# robotShield.net
KiCad netlist of a schematic drawn in Altium Designer
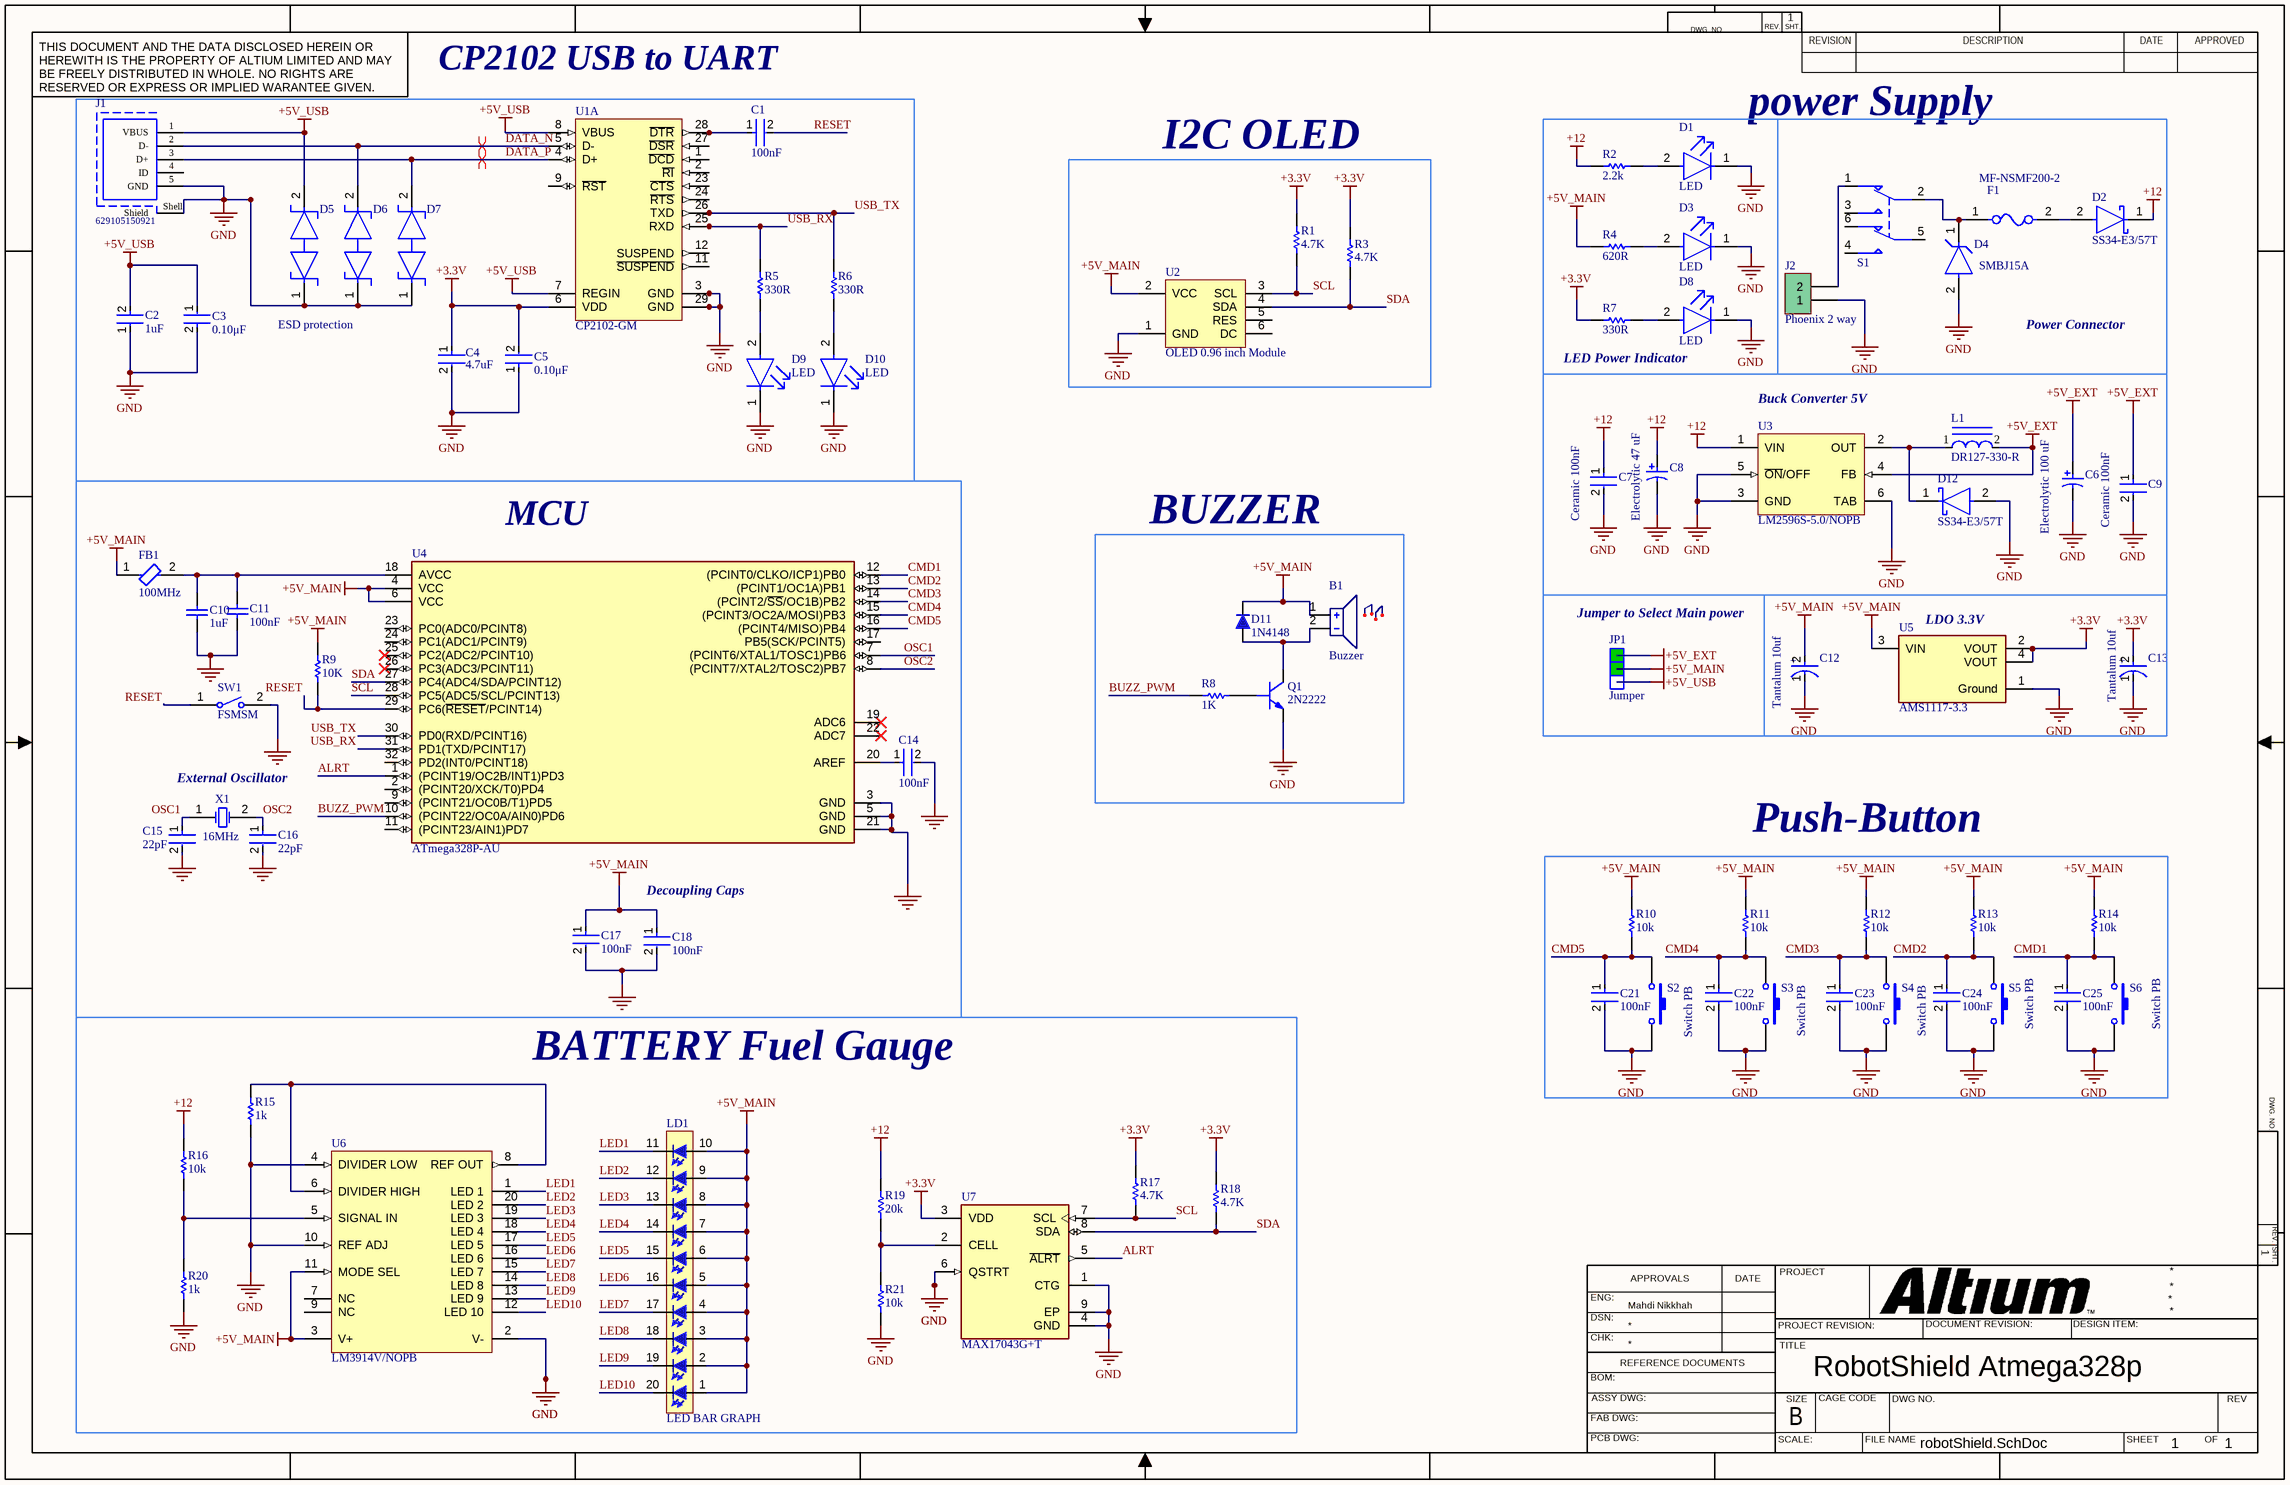
[diagram p0: robotShield.SchDoc]

(export (version "E")
  (design (tool "Eeschema 10.0.6"))
  (components
    (comp (ref "B1")
      (value "Buzzer")
      (footprint "Buzzer 3M")
      (libsource (lib "altium-import") (part "root_0_Buzzer New_"))
    )
    (comp (ref "C1")
      (value "100nF")
      (footprint "FP-GRM21B-0_15-MFG")
      (description "Chip Multilayer Ceramic Capacitors for General Purpose, 0805, 22uF, X5R, 15%, 20%, 6.3V")
      (fields (field (name "VOLTAGE") "6.3V") (field (name "TOLERANCE") "20%"))
      (libsource (lib "Altium Content Vault") (part "b4654b650e69147ec39a6b967a45e02"))
    )
    (comp (ref "C2")
      (value "1uF")
      (footprint "FP-GRM15-0_1-MFG")
      (description "CAP CER 1UF 10V X5R 0402")
      (fields
        (field (name "OCTOPART") "https://octopart.com/grm155r61a105ke15d-murata-197442")
        (field (name "MANUFACTURER PART NUMBER") "GRM155R61A105KE15D")
      )
      (libsource (lib "") (part "02cd4be3c70576c341d710602a673aa_1"))
    )
    (comp (ref "C3")
      (value "0.10μF")
      (footprint "FP-GRM15-MFG")
      (description "CAP CER 0.1UF 16V X7R 0402")
      (fields (field (name "MANUFACTURER PART NUMBER") "GRM155R71C104KA88D") (field (name "TOLERANCE") "10%"))
      (libsource (lib "") (part "236180d848d6139a670b325ea6854c9_1"))
    )
    (comp (ref "C4")
      (value "C1005X5R1A475K050BC")
      (footprint "FP-C1005-050-0_15-MFG")
      (description "CAP CER 4.7UF 10V X5R 0402")
      (fields (field (name "TOLERANCE") "10%") (field (name "CAPACITANCE") "4.7uF"))
      (libsource (lib "Altium Content Vault") (part "b4654b650e69147ec39a6b967a45e02"))
    )
    (comp (ref "C5")
      (value "0.10μF")
      (footprint "FP-GRM15-MFG")
      (description "CAP CER 0.1UF 16V X7R 0402")
      (fields (field (name "MANUFACTURER PART NUMBER") "GRM155R71C104KA88D") (field (name "TOLERANCE") "10%"))
      (libsource (lib "Altium Content Vault") (part "236180d848d6139a670b325ea6854c9"))
    )
    (comp (ref "C6")
      (value "Electrolytic 100 uF")
      (footprint "PNSC-EEEFK1C101P_L")
      (fields (field (name "MANUFACTURER") "Panasonic"))
      (libsource (lib "Altium Content Vault") (part "CAP-P-2"))
    )
    (comp (ref "C7")
      (value "Ceramic 100nF")
      (footprint "FP-1206-L_3_2_0_2-W_1_6_0-MFG")
      (description "General Purpose Ceramic Capacitor, 1206, 100nF, 10%, X7R, 15%, 50V")
      (fields (field (name "TOLERANCE") "10%") (field (name "VOLTAGE") "50V"))
      (libsource (lib "Altium Content Vault") (part "02cd4be3c70576c341d710602a673aa"))
    )
    (comp (ref "C8")
      (value "Electrolytic 47 uF")
      (footprint "PNSC-FT-V-53x53-2_V")
      (fields (field (name "PARTNUMBER") "EEE-FT1E470AR") (field (name "MANUFACTURER") "Panasonic"))
      (libsource (lib "Altium Content Vault") (part "PNSC-CAP-P-2"))
    )
    (comp (ref "C9")
      (value "Ceramic 100nF")
      (footprint "FP-1206-L_3_2_0_2-W_1_6_0-MFG")
      (description "General Purpose Ceramic Capacitor, 1206, 100nF, 10%, X7R, 15%, 50V")
      (fields (field (name "TOLERANCE") "10%") (field (name "VOLTAGE") "50V"))
      (libsource (lib "Altium Content Vault") (part "02cd4be3c70576c341d710602a673aa"))
    )
    (comp (ref "C10")
      (value "1uF")
      (footprint "CAPC3216X95X55NL15T25")
      (description "Chip Capacitor, 0.1 uF, +/- 10%, 50 V, -55 to 125 degC, 1206 (3216 Metric), RoHS, Tape and Reel")
      (fields (field (name "MANUFACTURER") "Murata"))
      (libsource (lib "Altium Content Vault") (part "CAP-NP-2"))
    )
    (comp (ref "C11")
      (value "100nF")
      (footprint "CAPC3216X95X55NL15T25")
      (description "Chip Capacitor, 0.1 uF, +/- 10%, 50 V, -55 to 125 degC, 1206 (3216 Metric), RoHS, Tape and Reel")
      (fields (field (name "MANUFACTURER") "Murata"))
      (libsource (lib "Altium Content Vault") (part "CAP-NP-2"))
    )
    (comp (ref "C12")
      (value "Tantalum 10uf")
      (footprint "FP-TAJA-MFG")
      (description "10uF 16V  ±10% 3Ω 1206  SMD Tantalum Capacitor")
      (fields (field (name "VOLTAGE") "16V") (field (name "TOLERANCE") "10%"))
      (libsource (lib "Altium Content Vault") (part "203bc49f2ac43e59fd269a8c329ed05"))
    )
    (comp (ref "C13")
      (value "Tantalum 10uf")
      (footprint "FP-TAJA-MFG")
      (description "10uF 16V  ±10% 3Ω 1206  SMD Tantalum Capacitor")
      (fields (field (name "VOLTAGE") "16V") (field (name "TOLERANCE") "10%"))
      (libsource (lib "Altium Content Vault") (part "203bc49f2ac43e59fd269a8c329ed05"))
    )
    (comp (ref "C14")
      (value "100nF")
      (footprint "FP-GRM21B-0_15-MFG")
      (description "Chip Multilayer Ceramic Capacitors for General Purpose, 0805, 22uF, X5R, 15%, 20%, 6.3V")
      (fields (field (name "VOLTAGE") "6.3V") (field (name "TOLERANCE") "20%"))
      (libsource (lib "Altium Content Vault") (part "b4654b650e69147ec39a6b967a45e02"))
    )
    (comp (ref "C15")
      (value "22pF")
      (footprint "FP-C1206C-EB-MFG")
      (description "CAP CER 22PF 100V 5% NP0 1206")
      (fields
        (field (name "MANUFACTURER PART NUMBER") "C1206C220J1GACTU")
        (field (name "MANUFACTURER") "KEMET")
      )
      (libsource (lib "Altium Content Vault") (part "b4654b650e69147ec39a6b967a45e02"))
    )
    (comp (ref "C16")
      (value "22pF")
      (footprint "FP-C1206C-EB-MFG")
      (description "CAP CER 22PF 100V 5% NP0 1206")
      (fields
        (field (name "MANUFACTURER PART NUMBER") "C1206C220J1GACTU")
        (field (name "MANUFACTURER") "KEMET")
      )
      (libsource (lib "Altium Content Vault") (part "b4654b650e69147ec39a6b967a45e02"))
    )
    (comp (ref "C17")
      (value "100nF")
      (footprint "FP-GRM21B-0_15-MFG")
      (description "Chip Multilayer Ceramic Capacitors for General Purpose, 0805, 22uF, X5R, 15%, 20%, 6.3V")
      (fields (field (name "VOLTAGE") "6.3V") (field (name "TOLERANCE") "20%"))
      (libsource (lib "Altium Content Vault") (part "b4654b650e69147ec39a6b967a45e02"))
    )
    (comp (ref "C18")
      (value "100nF")
      (footprint "FP-GRM21B-0_15-MFG")
      (description "Chip Multilayer Ceramic Capacitors for General Purpose, 0805, 22uF, X5R, 15%, 20%, 6.3V")
      (fields (field (name "VOLTAGE") "6.3V") (field (name "TOLERANCE") "20%"))
      (libsource (lib "Altium Content Vault") (part "b4654b650e69147ec39a6b967a45e02"))
    )
    (comp (ref "C21")
      (value "100nF")
      (footprint "FP-GRM21B-0_15-MFG")
      (description "Chip Multilayer Ceramic Capacitors for General Purpose, 0805, 22uF, X5R, 15%, 20%, 6.3V")
      (fields (field (name "VOLTAGE") "6.3V") (field (name "TOLERANCE") "20%"))
      (libsource (lib "Altium Content Vault") (part "b4654b650e69147ec39a6b967a45e02"))
    )
    (comp (ref "C22")
      (value "100nF")
      (footprint "FP-GRM21B-0_15-MFG")
      (description "Chip Multilayer Ceramic Capacitors for General Purpose, 0805, 22uF, X5R, 15%, 20%, 6.3V")
      (fields (field (name "VOLTAGE") "6.3V") (field (name "TOLERANCE") "20%"))
      (libsource (lib "Altium Content Vault") (part "b4654b650e69147ec39a6b967a45e02"))
    )
    (comp (ref "C23")
      (value "100nF")
      (footprint "FP-GRM21B-0_15-MFG")
      (description "Chip Multilayer Ceramic Capacitors for General Purpose, 0805, 22uF, X5R, 15%, 20%, 6.3V")
      (fields (field (name "VOLTAGE") "6.3V") (field (name "TOLERANCE") "20%"))
      (libsource (lib "Altium Content Vault") (part "b4654b650e69147ec39a6b967a45e02"))
    )
    (comp (ref "C24")
      (value "100nF")
      (footprint "FP-GRM21B-0_15-MFG")
      (description "Chip Multilayer Ceramic Capacitors for General Purpose, 0805, 22uF, X5R, 15%, 20%, 6.3V")
      (fields (field (name "VOLTAGE") "6.3V") (field (name "TOLERANCE") "20%"))
      (libsource (lib "Altium Content Vault") (part "b4654b650e69147ec39a6b967a45e02"))
    )
    (comp (ref "C25")
      (value "100nF")
      (footprint "FP-GRM21B-0_15-MFG")
      (description "Chip Multilayer Ceramic Capacitors for General Purpose, 0805, 22uF, X5R, 15%, 20%, 6.3V")
      (fields (field (name "VOLTAGE") "6.3V") (field (name "TOLERANCE") "20%"))
      (libsource (lib "Altium Content Vault") (part "b4654b650e69147ec39a6b967a45e02"))
    )
    (comp (ref "D1")
      (value "LED")
      (footprint "FP-HSMG-C150-MFG")
      (description "LED GREEN DIFFUSED 1206 SMD")
      (fields (field (name "MANUFACTURER PART NUMBER") "HSMG-C150") (field (name "MANUFACTURER") "Broadcom"))
      (libsource (lib "Altium Content Vault") (part "8706943c75ba83719d021d2fdc84c58"))
    )
    (comp (ref "D2")
      (value "SS34-E3/57T")
      (footprint "FP-95402-MFG")
      (description "DIODE SCHOTTKY 40V 3A DO214AB")
      (fields
        (field (name "MANUFACTURER") "Vishay")
        (field (name "OCTOPART") "https://octopart.com/ss34-e3%2F57t-vishay-39552907")
      )
      (libsource (lib "Altium Content Vault") (part "1d6ec82d83fb6aee721767c19dac4b9"))
    )
    (comp (ref "D3")
      (value "LED")
      (footprint "FP-HSMG-C150-MFG")
      (description "LED GREEN DIFFUSED 1206 SMD")
      (fields (field (name "MANUFACTURER PART NUMBER") "HSMG-C150") (field (name "MANUFACTURER") "Broadcom"))
      (libsource (lib "Altium Content Vault") (part "8706943c75ba83719d021d2fdc84c58"))
    )
    (comp (ref "D4")
      (value "SMBJ15A")
      (footprint "FP-SMBJ-MFG")
      (description "TVS DIODE 15VWM 24.4VC SMB")
      (libsource (lib "Altium Content Vault") (part "f813f71cba58e380607f5dd3caf9714"))
    )
    (comp (ref "D5")
      (value "TPD1E10B06DPYR")
      (footprint "FP-DPY0002A-MFG")
      (description "TVS DIODE 5.5V 14V 2X1SON")
      (libsource (lib "Altium Content Vault") (part "208e19b57522434895fa003e5d5b197"))
    )
    (comp (ref "D6")
      (value "TPD1E10B06DPYR")
      (footprint "FP-DPY0002A-MFG")
      (description "TVS DIODE 5.5V 14V 2X1SON")
      (libsource (lib "Altium Content Vault") (part "208e19b57522434895fa003e5d5b197"))
    )
    (comp (ref "D7")
      (value "TPD1E10B06DPYR")
      (footprint "FP-DPY0002A-MFG")
      (description "TVS DIODE 5.5V 14V 2X1SON")
      (libsource (lib "Altium Content Vault") (part "208e19b57522434895fa003e5d5b197"))
    )
    (comp (ref "D8")
      (value "LED")
      (footprint "FP-HSMG-C150-MFG")
      (description "LED GREEN DIFFUSED 1206 SMD")
      (fields (field (name "MANUFACTURER PART NUMBER") "HSMG-C150") (field (name "MANUFACTURER") "Broadcom"))
      (libsource (lib "Altium Content Vault") (part "8706943c75ba83719d021d2fdc84c58"))
    )
    (comp (ref "D9")
      (value "LED")
      (footprint "FP-HSMG-C150-MFG")
      (description "LED GREEN DIFFUSED 1206 SMD")
      (fields (field (name "MANUFACTURER PART NUMBER") "HSMG-C150") (field (name "MANUFACTURER") "Broadcom"))
      (libsource (lib "Altium Content Vault") (part "8706943c75ba83719d021d2fdc84c58"))
    )
    (comp (ref "D10")
      (value "LED")
      (footprint "FP-HSMG-C150-MFG")
      (description "LED GREEN DIFFUSED 1206 SMD")
      (fields (field (name "MANUFACTURER PART NUMBER") "HSMG-C150") (field (name "MANUFACTURER") "Broadcom"))
      (libsource (lib "Altium Content Vault") (part "8706943c75ba83719d021d2fdc84c58"))
    )
    (comp (ref "D11")
      (value "1N4148")
      (footprint "SOD-123")
      (libsource (lib "altium-import") (part "root_1_1N4148_"))
    )
    (comp (ref "D12")
      (value "SS34-E3/57T")
      (footprint "FP-95402-MFG")
      (description "DIODE SCHOTTKY 40V 3A DO214AB")
      (fields
        (field (name "MANUFACTURER") "Vishay")
        (field (name "OCTOPART") "https://octopart.com/ss34-e3%2F57t-vishay-39552907")
      )
      (libsource (lib "Altium Content Vault") (part "1d6ec82d83fb6aee721767c19dac4b9"))
    )
    (comp (ref "F1")
      (value "MF-NSMF200-2")
      (footprint "FP-MF-NSMF200-2-MFG")
      (description "PTC RESET FUSE 12V 2A 1206")
      (fields
        (field (name "MANUFACTURER") "Bourns Inc.")
        (field (name "OCTOPART") "https://octopart.com/mf-nsmf200-2-bourns-90790")
      )
      (libsource (lib "Altium Content Vault") (part "5bcf9b9f640e542cf0359d10258e979"))
    )
    (comp (ref "FB1")
      (value "100MHz")
      (footprint "FP-BLM21-0_2-t0_85-e0_5-IPC_A")
      (description "FERRITE BEAD 120 OHM 0805 1LN")
      (fields (field (name "TOLERANCE") "25%"))
      (libsource (lib "Altium Content Vault") (part "5f30dd21d616792df468990f7003faa"))
    )
    (comp (ref "J1")
      (value "629105150921")
      (footprint "629105150921")
      (description "Micro USB 2.0 Type AB Receptacle WR-COM, Horizontal, SMT")
      (fields (field (name "PUBLISHER") "Wurth Elektronik"))
      (libsource (lib "USB") (part "629105150921"))
    )
    (comp (ref "J2")
      (value "Phoenix 2 way")
      (footprint "Phoenix 2 way 5.08mm V")
      (libsource (lib "altium-import") (part "root_1_Phoenix 2 way_"))
    )
    (comp (ref "JP1")
      (value "Jumper")
      (footprint "jumper selector")
      (description "Jumper Selector")
      (libsource (lib "altium-import") (part "root_0_Jumper Selector_"))
    )
    (comp (ref "L1")
      (value "DR127-330-R")
      (footprint "FP-DR127-MFG")
      (description "DR127-330-R Inductor Power Shielded Drum Core 33uH 20% 100KHz Ferrite 3.23A 60mOhm DCR T/R")
      (fields (field (name "TOLERANCE") "20%"))
      (libsource (lib "Altium Content Vault") (part "595efa879b4242f50b2b19a2702faec"))
    )
    (comp (ref "LD1")
      (value "LED BAR GRAPH")
      (footprint "LED BAR GRAPH W")
      (libsource (lib "altium-import") (part "root_2_LED BAR GRAPH_"))
    )
    (comp (ref "Q1")
      (value "2N2222")
      (footprint "SOT-23")
      (libsource (lib "altium-import") (part "root_0_2N2222_"))
    )
    (comp (ref "R1")
      (value "4.7K")
      (footprint "RESC2013X60X35ML10T20")
      (description "Chip Resistor, 1 KOhm, +/- 1%, 125 mW, -55 to 155 degC, 0805 (2012 Metric), RoHS, Tape and Reel")
      (fields (field (name "TOLERANCE") "1%") (field (name "MANUFACTURER") "Yageo"))
      (libsource (lib "Altium Content Vault") (part "RES-2"))
    )
    (comp (ref "R2")
      (value "2.2k")
      (footprint "RESC2013X60X35ML10T20")
      (description "Chip Resistor, 1 KOhm, +/- 1%, 125 mW, -55 to 155 degC, 0805 (2012 Metric), RoHS, Tape and Reel")
      (fields (field (name "TOLERANCE") "1%") (field (name "MANUFACTURER") "Yageo"))
      (libsource (lib "Altium Content Vault") (part "RES-2"))
    )
    (comp (ref "R3")
      (value "4.7K")
      (footprint "RESC2013X60X35ML10T20")
      (description "Chip Resistor, 1 KOhm, +/- 1%, 125 mW, -55 to 155 degC, 0805 (2012 Metric), RoHS, Tape and Reel")
      (fields (field (name "TOLERANCE") "1%") (field (name "MANUFACTURER") "Yageo"))
      (libsource (lib "Altium Content Vault") (part "RES-2"))
    )
    (comp (ref "R4")
      (value "620R")
      (footprint "RESC2013X60X35ML10T20")
      (description "Chip Resistor, 1 KOhm, +/- 1%, 125 mW, -55 to 155 degC, 0805 (2012 Metric), RoHS, Tape and Reel")
      (fields (field (name "TOLERANCE") "1%") (field (name "MANUFACTURER") "Yageo"))
      (libsource (lib "Altium Content Vault") (part "RES-2"))
    )
    (comp (ref "R5")
      (value "330R")
      (footprint "RESC2013X60X35ML10T20")
      (description "Chip Resistor, 1 KOhm, +/- 1%, 125 mW, -55 to 155 degC, 0805 (2012 Metric), RoHS, Tape and Reel")
      (fields (field (name "TOLERANCE") "1%") (field (name "MANUFACTURER") "Yageo"))
      (libsource (lib "Altium Content Vault") (part "RES-2"))
    )
    (comp (ref "R6")
      (value "330R")
      (footprint "RESC2013X60X35ML10T20")
      (description "Chip Resistor, 1 KOhm, +/- 1%, 125 mW, -55 to 155 degC, 0805 (2012 Metric), RoHS, Tape and Reel")
      (fields (field (name "TOLERANCE") "1%") (field (name "MANUFACTURER") "Yageo"))
      (libsource (lib "Altium Content Vault") (part "RES-2"))
    )
    (comp (ref "R7")
      (value "330R")
      (footprint "RESC2013X60X35ML10T20")
      (description "Chip Resistor, 1 KOhm, +/- 1%, 125 mW, -55 to 155 degC, 0805 (2012 Metric), RoHS, Tape and Reel")
      (fields (field (name "TOLERANCE") "1%") (field (name "MANUFACTURER") "Yageo"))
      (libsource (lib "Altium Content Vault") (part "RES-2"))
    )
    (comp (ref "R8")
      (value "1K")
      (footprint "RESC2013X60X35ML10T20")
      (description "Chip Resistor, 1 KOhm, +/- 1%, 125 mW, -55 to 155 degC, 0805 (2012 Metric), RoHS, Tape and Reel")
      (fields (field (name "TOLERANCE") "1%") (field (name "MANUFACTURER") "Yageo"))
      (libsource (lib "Altium Content Vault") (part "RES-2"))
    )
    (comp (ref "R9")
      (value "10K")
      (footprint "RESC3116X65X40ML10T20")
      (description "Chip Resistor, 10 KOhm, +/- 1%, 0.25 W, -55 to 155 degC, 1206 (3216 Metric), RoHS, Tape and Reel")
      (fields (field (name "TOLERANCE") "1%") (field (name "MANUFACTURER") "Yageo"))
      (libsource (lib "Altium Content Vault") (part "RES-2"))
    )
    (comp (ref "R10")
      (value "10k")
      (footprint "RESC2013X60X35ML10T20")
      (description "Chip Resistor, 1 KOhm, +/- 1%, 125 mW, -55 to 155 degC, 0805 (2012 Metric), RoHS, Tape and Reel")
      (fields (field (name "TOLERANCE") "1%") (field (name "MANUFACTURER") "Yageo"))
      (libsource (lib "Altium Content Vault") (part "RES-2"))
    )
    (comp (ref "R11")
      (value "10k")
      (footprint "RESC2013X60X35ML10T20")
      (description "Chip Resistor, 1 KOhm, +/- 1%, 125 mW, -55 to 155 degC, 0805 (2012 Metric), RoHS, Tape and Reel")
      (fields (field (name "TOLERANCE") "1%") (field (name "MANUFACTURER") "Yageo"))
      (libsource (lib "Altium Content Vault") (part "RES-2"))
    )
    (comp (ref "R12")
      (value "10k")
      (footprint "RESC2013X60X35ML10T20")
      (description "Chip Resistor, 1 KOhm, +/- 1%, 125 mW, -55 to 155 degC, 0805 (2012 Metric), RoHS, Tape and Reel")
      (fields (field (name "TOLERANCE") "1%") (field (name "MANUFACTURER") "Yageo"))
      (libsource (lib "Altium Content Vault") (part "RES-2"))
    )
    (comp (ref "R13")
      (value "10k")
      (footprint "RESC2013X60X35ML10T20")
      (description "Chip Resistor, 1 KOhm, +/- 1%, 125 mW, -55 to 155 degC, 0805 (2012 Metric), RoHS, Tape and Reel")
      (fields (field (name "TOLERANCE") "1%") (field (name "MANUFACTURER") "Yageo"))
      (libsource (lib "Altium Content Vault") (part "RES-2"))
    )
    (comp (ref "R14")
      (value "10k")
      (footprint "RESC2013X60X35ML10T20")
      (description "Chip Resistor, 1 KOhm, +/- 1%, 125 mW, -55 to 155 degC, 0805 (2012 Metric), RoHS, Tape and Reel")
      (fields (field (name "TOLERANCE") "1%") (field (name "MANUFACTURER") "Yageo"))
      (libsource (lib "Altium Content Vault") (part "RES-2"))
    )
    (comp (ref "R15")
      (value "1k")
      (footprint "RESC2013X60X35ML10T20")
      (description "Chip Resistor, 1 KOhm, +/- 1%, 125 mW, -55 to 155 degC, 0805 (2012 Metric), RoHS, Tape and Reel")
      (fields (field (name "TOLERANCE") "1%") (field (name "MANUFACTURER") "Yageo"))
      (libsource (lib "Altium Content Vault") (part "RES-2"))
    )
    (comp (ref "R16")
      (value "10k")
      (footprint "RESC2013X60X35ML10T20")
      (description "Chip Resistor, 1 KOhm, +/- 1%, 125 mW, -55 to 155 degC, 0805 (2012 Metric), RoHS, Tape and Reel")
      (fields (field (name "TOLERANCE") "1%") (field (name "MANUFACTURER") "Yageo"))
      (libsource (lib "Altium Content Vault") (part "RES-2"))
    )
    (comp (ref "R17")
      (value "4.7K")
      (footprint "RESC2013X60X35ML10T20")
      (description "Chip Resistor, 1 KOhm, +/- 1%, 125 mW, -55 to 155 degC, 0805 (2012 Metric), RoHS, Tape and Reel")
      (fields (field (name "TOLERANCE") "1%") (field (name "MANUFACTURER") "Yageo"))
      (libsource (lib "Altium Content Vault") (part "RES-2"))
    )
    (comp (ref "R18")
      (value "4.7K")
      (footprint "RESC2013X60X35ML10T20")
      (description "Chip Resistor, 1 KOhm, +/- 1%, 125 mW, -55 to 155 degC, 0805 (2012 Metric), RoHS, Tape and Reel")
      (fields (field (name "TOLERANCE") "1%") (field (name "MANUFACTURER") "Yageo"))
      (libsource (lib "Altium Content Vault") (part "RES-2"))
    )
    (comp (ref "R19")
      (value "20k")
      (footprint "RESC2013X60X35ML10T20")
      (description "Chip Resistor, 1 KOhm, +/- 1%, 125 mW, -55 to 155 degC, 0805 (2012 Metric), RoHS, Tape and Reel")
      (fields (field (name "TOLERANCE") "1%") (field (name "MANUFACTURER") "Yageo"))
      (libsource (lib "Altium Content Vault") (part "RES-2"))
    )
    (comp (ref "R20")
      (value "1k")
      (footprint "RESC2013X60X35ML10T20")
      (description "Chip Resistor, 1 KOhm, +/- 1%, 125 mW, -55 to 155 degC, 0805 (2012 Metric), RoHS, Tape and Reel")
      (fields (field (name "TOLERANCE") "1%") (field (name "MANUFACTURER") "Yageo"))
      (libsource (lib "Altium Content Vault") (part "RES-2"))
    )
    (comp (ref "R21")
      (value "10k")
      (footprint "RESC2013X60X35ML10T20")
      (description "Chip Resistor, 1 KOhm, +/- 1%, 125 mW, -55 to 155 degC, 0805 (2012 Metric), RoHS, Tape and Reel")
      (fields (field (name "TOLERANCE") "1%") (field (name "MANUFACTURER") "Yageo"))
      (libsource (lib "Altium Content Vault") (part "RES-2"))
    )
    (comp (ref "S1")
      (value "Double Switch")
      (footprint "Switch - DPDT")
      (description "DPDT Switch")
      (fields (field (name "DESIGNER") "Eng. Saeid Jorablo"))
      (libsource (lib "altium-import") (part "root_0_SW_DPDT_"))
    )
    (comp (ref "S2")
      (value "Switch PB")
      (footprint "SW-PB")
      (description "Push Button Switch")
      (libsource (lib "General 2") (part "Switch PB"))
    )
    (comp (ref "S3")
      (value "Switch PB")
      (footprint "SW-PB")
      (description "Push Button Switch")
      (libsource (lib "General 2") (part "Switch PB"))
    )
    (comp (ref "S4")
      (value "Switch PB")
      (footprint "SW-PB")
      (description "Push Button Switch")
      (libsource (lib "General 2") (part "Switch PB"))
    )
    (comp (ref "S5")
      (value "Switch PB")
      (footprint "SW-PB")
      (description "Push Button Switch")
      (libsource (lib "General 2") (part "Switch PB"))
    )
    (comp (ref "S6")
      (value "Switch PB")
      (footprint "SW-PB")
      (description "Push Button Switch")
      (libsource (lib "General 2") (part "Switch PB"))
    )
    (comp (ref "SW1")
      (value "FSMSM")
      (footprint "TECO-FSMSM-2_V")
      (description "FSMSM Push Button Switch, 50 mA, -35 to 85 degC, 2-Pin SMD, RoHS, Bulk")
      (fields (field (name "MANUFACTURER") "TE Connectivity"))
      (libsource (lib "Altium Content Vault") (part "SW-SPST-2_C"))
    )
    (comp (ref "U1")
      (value "CP2102-GM")
      (footprint "SLAB-QFN-28-3125x3125TP_N")
      (description "Single-Chip USB to UART Bridge, 1024 Bytes EEPROM, -40 to 85 degC, 28-pin QFN, Tube")
      (fields (field (name "MANUFACTURER") "Silicon Labs"))
      (libsource (lib "Altium Content Vault") (part "SLAB-CP210X-QFN-28-29"))
    )
    (comp (ref "U2")
      (value "OLED 0.96 inch Module")
      (footprint "OLED 0.96 inch Module")
      (libsource (lib "altium-import") (part "root_0_OLED 0.96 inch Module_"))
    )
    (comp (ref "U3")
      (value "LM2596S-5.0/NOPB")
      (footprint "KTT0005B_M")
      (description "SIMPLE SWITCHER® Power Converter 150 KHz 3A Step-Down Voltage Regulator, 5-pin TO-263, Pb-Free")
      (fields (field (name "MANUFACTURER") "Texas Instruments"))
      (libsource (lib "Altium Content Vault") (part "PM-REG-LM2575HVS-12"))
    )
    (comp (ref "U4")
      (value "ATmega328P-AU")
      (footprint "FP-32A-MFG")
      (description "IC MCU 8BIT 32KB FLASH 32TQFP")
      (fields
        (field (name "MANUFACTURER") "Microchip")
        (field (name "OCTOPART") "https://octopart.com/atmega328p-au-microchip-77760215")
      )
      (libsource (lib "Altium Content Vault") (part "f5fbdcb2c0c597ef7d3dd1575aef21a"))
    )
    (comp (ref "U5")
      (value "AMS1117-3.3")
      (footprint "FP-AMS1117-IPC_C")
      (description "LDO Voltage Regulators 1A, 3.3V")
      (fields
        (field (name "OCTOPART") "https://octopart.com/ams1117-3.3-advanced+monolithic+systems-25899300")
        (field (name "MANUFACTURER") "Advanced Monolithic Systems")
      )
      (libsource (lib "Altium Content Vault") (part "8bdbb5f8e77002000e30dd2845d0354"))
    )
    (comp (ref "U6")
      (value "LM3914V/NOPB")
      (footprint "FN0020A_L")
      (description "Dot/Bar Display Driver, 20-pin PLCC, Pb-Free")
      (fields (field (name "MANUFACTURER") "Texas Instruments"))
      (libsource (lib "Altium Content Vault") (part "IN-DD-LM3914-20"))
    )
    (comp (ref "U7")
      (value "MAX17043G+T")
      (footprint "FP-T823-1-MFG")
      (description "IC 2-WIRE FG MODEL GAUGE LO BATT")
      (fields
        (field (name "MANUFACTURER") "Maxim")
        (field (name "OCTOPART") "https://octopart.com/max17043g%2Bt-maxim+integrated-43979038")
      )
      (libsource (lib "Altium Content Vault") (part "35642440c5a18a865b7fad9439d5373"))
    )
    (comp (ref "X1")
      (value "16MHz")
      (footprint "FOX-FOXSDLF160-20_V")
      (libsource (lib "Altium Content Vault") (part "XTAL_1-2-2"))
    )
  )
  (nets
    (net (code "1") (name "+3.3V") (class "Default")
      (node (ref "C13") (pin "2") (pinfunction "A_2") (pintype "passive"))
      (node (ref "C4") (pin "1") (pinfunction "1_1") (pintype "passive"))
      (node (ref "C5") (pin "2") (pinfunction "2_2") (pintype "passive"))
      (node (ref "R1") (pin "2") (pinfunction "2_2") (pintype "passive"))
      (node (ref "R17") (pin "2") (pinfunction "2_2") (pintype "passive"))
      (node (ref "R18") (pin "2") (pinfunction "2_2") (pintype "passive"))
      (node (ref "R3") (pin "2") (pinfunction "2_2") (pintype "passive"))
      (node (ref "R7") (pin "1") (pinfunction "1_1") (pintype "passive"))
      (node (ref "U1") (pin "6") (pinfunction "VDD_6") (pintype "power_in"))
      (node (ref "U5") (pin "2") (pinfunction "VOUT_2") (pintype "passive"))
      (node (ref "U5") (pin "4") (pinfunction "VOUT_4") (pintype "passive"))
      (node (ref "U7") (pin "3") (pinfunction "VDD_3") (pintype "power_in"))
    )
    (net (code "2") (name "+5V_EXT") (class "Default")
      (node (ref "C6") (pin "1") (pinfunction "1_1") (pintype "passive"))
      (node (ref "C9") (pin "1") (pinfunction "1_1") (pintype "passive"))
      (node (ref "JP1") (pin "1") (pinfunction "1_1") (pintype "passive"))
      (node (ref "L1") (pin "2") (pinfunction "2_2") (pintype "passive"))
      (node (ref "U3") (pin "4") (pinfunction "FB_4") (pintype "input"))
    )
    (net (code "3") (name "+5V_MAIN") (class "Default")
      (node (ref "B1") (pin "1") (pinfunction "1_1") (pintype "passive"))
      (node (ref "C12") (pin "2") (pinfunction "A_2") (pintype "passive"))
      (node (ref "C17") (pin "1") (pinfunction "1_1") (pintype "passive"))
      (node (ref "C18") (pin "1") (pinfunction "1_1") (pintype "passive"))
      (node (ref "D11") (pin "2") (pinfunction "K_2") (pintype "passive"))
      (node (ref "FB1") (pin "1") (pinfunction "1_1") (pintype "passive"))
      (node (ref "JP1") (pin "2") (pinfunction "2_2") (pintype "passive"))
      (node (ref "LD1") (pin "1") (pinfunction "A_1") (pintype "passive"))
      (node (ref "LD1") (pin "10") (pinfunction "A_10") (pintype "passive"))
      (node (ref "LD1") (pin "2") (pinfunction "A_2") (pintype "passive"))
      (node (ref "LD1") (pin "3") (pinfunction "A_3") (pintype "passive"))
      (node (ref "LD1") (pin "4") (pinfunction "A_4") (pintype "passive"))
      (node (ref "LD1") (pin "5") (pinfunction "A_5") (pintype "passive"))
      (node (ref "LD1") (pin "6") (pinfunction "A_6") (pintype "passive"))
      (node (ref "LD1") (pin "7") (pinfunction "A_7") (pintype "passive"))
      (node (ref "LD1") (pin "8") (pinfunction "A_8") (pintype "passive"))
      (node (ref "LD1") (pin "9") (pinfunction "A_9") (pintype "passive"))
      (node (ref "R10") (pin "2") (pinfunction "2_2") (pintype "passive"))
      (node (ref "R11") (pin "2") (pinfunction "2_2") (pintype "passive"))
      (node (ref "R12") (pin "2") (pinfunction "2_2") (pintype "passive"))
      (node (ref "R13") (pin "2") (pinfunction "2_2") (pintype "passive"))
      (node (ref "R14") (pin "2") (pinfunction "2_2") (pintype "passive"))
      (node (ref "R4") (pin "1") (pinfunction "1_1") (pintype "passive"))
      (node (ref "R9") (pin "1") (pinfunction "1_1") (pintype "passive"))
      (node (ref "U2") (pin "2") (pinfunction "VCC_2") (pintype "passive"))
      (node (ref "U4") (pin "4") (pinfunction "VCC_4") (pintype "power_in"))
      (node (ref "U4") (pin "6") (pinfunction "VCC_6") (pintype "power_in"))
      (node (ref "U5") (pin "3") (pinfunction "VIN_3") (pintype "power_in"))
      (node (ref "U6") (pin "11") (pinfunction "MODE_SEL_11") (pintype "input"))
      (node (ref "U6") (pin "3") (pinfunction "V+_3") (pintype "power_in"))
    )
    (net (code "4") (name "+5V_USB") (class "Default")
      (node (ref "C2") (pin "2") (pinfunction "2_2") (pintype "passive"))
      (node (ref "C3") (pin "1") (pinfunction "1_1") (pintype "passive"))
      (node (ref "D5") (pin "2") (pinfunction "2_2") (pintype "passive"))
      (node (ref "J1") (pin "1") (pinfunction "VBUS_1") (pintype "passive"))
      (node (ref "JP1") (pin "3") (pinfunction "3_3") (pintype "passive"))
      (node (ref "U1") (pin "7") (pinfunction "REGIN_7") (pintype "power_in"))
      (node (ref "U1") (pin "8") (pinfunction "VBUS_8") (pintype "input"))
    )
    (net (code "5") (name "+12") (class "Default")
      (node (ref "C7") (pin "1") (pinfunction "1_1") (pintype "passive"))
      (node (ref "C8") (pin "1") (pinfunction "1_1") (pintype "passive"))
      (node (ref "D2") (pin "1") (pinfunction "C_1") (pintype "passive"))
      (node (ref "R16") (pin "2") (pinfunction "2_2") (pintype "passive"))
      (node (ref "R19") (pin "2") (pinfunction "2_2") (pintype "passive"))
      (node (ref "R2") (pin "1") (pinfunction "1_1") (pintype "passive"))
      (node (ref "U3") (pin "1") (pinfunction "VIN_1") (pintype "power_in"))
    )
    (net (code "6") (name "/ALRT") (class "Default")
      (node (ref "U4") (pin "1") (pinfunction "(PCINT19/OC2B/INT1)PD3_1") (pintype "bidirectional"))
      (node (ref "U7") (pin "5") (pinfunction "~{ALRT}_5") (pintype "output"))
    )
    (net (code "7") (name "/BUZZ_PWM") (class "Default")
      (node (ref "R8") (pin "2") (pinfunction "2_2") (pintype "passive"))
      (node (ref "U4") (pin "10") (pinfunction "(PCINT22/OC0A/AIN0)PD6_10") (pintype "bidirectional"))
    )
    (net (code "8") (name "/CMD1") (class "Default")
      (node (ref "C25") (pin "1") (pinfunction "1_1") (pintype "passive"))
      (node (ref "R14") (pin "1") (pinfunction "1_1") (pintype "passive"))
      (node (ref "S6") (pin "1") (pinfunction "1_1") (pintype "passive"))
      (node (ref "U4") (pin "12") (pinfunction "(PCINT0/CLKO/ICP1)PB0_12") (pintype "bidirectional"))
    )
    (net (code "9") (name "/CMD2") (class "Default")
      (node (ref "C24") (pin "1") (pinfunction "1_1") (pintype "passive"))
      (node (ref "R13") (pin "1") (pinfunction "1_1") (pintype "passive"))
      (node (ref "S5") (pin "1") (pinfunction "1_1") (pintype "passive"))
      (node (ref "U4") (pin "13") (pinfunction "(PCINT1/OC1A)PB1_13") (pintype "bidirectional"))
    )
    (net (code "10") (name "/CMD3") (class "Default")
      (node (ref "C23") (pin "1") (pinfunction "1_1") (pintype "passive"))
      (node (ref "R12") (pin "1") (pinfunction "1_1") (pintype "passive"))
      (node (ref "S4") (pin "1") (pinfunction "1_1") (pintype "passive"))
      (node (ref "U4") (pin "14") (pinfunction "(PCINT2/~{SS}/OC1B)PB2_14") (pintype "bidirectional"))
    )
    (net (code "11") (name "/CMD4") (class "Default")
      (node (ref "C22") (pin "1") (pinfunction "1_1") (pintype "passive"))
      (node (ref "R11") (pin "1") (pinfunction "1_1") (pintype "passive"))
      (node (ref "S3") (pin "1") (pinfunction "1_1") (pintype "passive"))
      (node (ref "U4") (pin "15") (pinfunction "(PCINT3/OC2A/MOSI)PB3_15") (pintype "bidirectional"))
    )
    (net (code "12") (name "/CMD5") (class "Default")
      (node (ref "C21") (pin "1") (pinfunction "1_1") (pintype "passive"))
      (node (ref "R10") (pin "1") (pinfunction "1_1") (pintype "passive"))
      (node (ref "S2") (pin "1") (pinfunction "1_1") (pintype "passive"))
      (node (ref "U4") (pin "16") (pinfunction "(PCINT4/MISO)PB4_16") (pintype "bidirectional"))
    )
    (net (code "13") (name "/DATA_N") (class "Default")
      (node (ref "D6") (pin "2") (pinfunction "2_2") (pintype "passive"))
      (node (ref "J1") (pin "2") (pinfunction "D-_2") (pintype "passive"))
      (node (ref "U1") (pin "5") (pinfunction "D-_5") (pintype "bidirectional"))
    )
    (net (code "14") (name "/DATA_P") (class "Default")
      (node (ref "D7") (pin "2") (pinfunction "2_2") (pintype "passive"))
      (node (ref "J1") (pin "3") (pinfunction "D+_3") (pintype "passive"))
      (node (ref "U1") (pin "4") (pinfunction "D+_4") (pintype "bidirectional"))
    )
    (net (code "15") (name "/LED1") (class "Default")
      (node (ref "LD1") (pin "11") (pinfunction "K_11") (pintype "passive"))
      (node (ref "U6") (pin "1") (pinfunction "LED_1_1") (pintype "open_collector"))
    )
    (net (code "16") (name "/LED2") (class "Default")
      (node (ref "LD1") (pin "12") (pinfunction "K_12") (pintype "passive"))
      (node (ref "U6") (pin "20") (pinfunction "LED_2_20") (pintype "open_collector"))
    )
    (net (code "17") (name "/LED3") (class "Default")
      (node (ref "LD1") (pin "13") (pinfunction "K_13") (pintype "passive"))
      (node (ref "U6") (pin "19") (pinfunction "LED_3_19") (pintype "open_collector"))
    )
    (net (code "18") (name "/LED4") (class "Default")
      (node (ref "LD1") (pin "14") (pinfunction "K_14") (pintype "passive"))
      (node (ref "U6") (pin "18") (pinfunction "LED_4_18") (pintype "open_collector"))
    )
    (net (code "19") (name "/LED5") (class "Default")
      (node (ref "LD1") (pin "15") (pinfunction "K_15") (pintype "passive"))
      (node (ref "U6") (pin "17") (pinfunction "LED_5_17") (pintype "open_collector"))
    )
    (net (code "20") (name "/LED6") (class "Default")
      (node (ref "LD1") (pin "16") (pinfunction "K_16") (pintype "passive"))
      (node (ref "U6") (pin "16") (pinfunction "LED_6_16") (pintype "open_collector"))
    )
    (net (code "21") (name "/LED7") (class "Default")
      (node (ref "LD1") (pin "17") (pinfunction "K_17") (pintype "passive"))
      (node (ref "U6") (pin "15") (pinfunction "LED_7_15") (pintype "open_collector"))
    )
    (net (code "22") (name "/LED8") (class "Default")
      (node (ref "LD1") (pin "18") (pinfunction "K_18") (pintype "passive"))
      (node (ref "U6") (pin "14") (pinfunction "LED_8_14") (pintype "open_collector"))
    )
    (net (code "23") (name "/LED9") (class "Default")
      (node (ref "LD1") (pin "19") (pinfunction "K_19") (pintype "passive"))
      (node (ref "U6") (pin "13") (pinfunction "LED_9_13") (pintype "open_collector"))
    )
    (net (code "24") (name "/LED10") (class "Default")
      (node (ref "LD1") (pin "20") (pinfunction "K_20") (pintype "passive"))
      (node (ref "U6") (pin "12") (pinfunction "LED_10_12") (pintype "open_collector"))
    )
    (net (code "25") (name "/OSC1") (class "Default")
      (node (ref "C15") (pin "1") (pinfunction "1_1") (pintype "passive"))
      (node (ref "U4") (pin "7") (pinfunction "(PCINT6/XTAL1/TOSC1)PB6_7") (pintype "bidirectional"))
      (node (ref "X1") (pin "1") (pinfunction "X1_1") (pintype "passive"))
    )
    (net (code "26") (name "/OSC2") (class "Default")
      (node (ref "C16") (pin "1") (pinfunction "1_1") (pintype "passive"))
      (node (ref "U4") (pin "8") (pinfunction "(PCINT7/XTAL2/TOSC2)PB7_8") (pintype "bidirectional"))
      (node (ref "X1") (pin "2") (pinfunction "X2_2") (pintype "passive"))
    )
    (net (code "27") (name "/RESET") (class "Default")
      (node (ref "C1") (pin "2") (pinfunction "2_2") (pintype "passive"))
      (node (ref "R9") (pin "2") (pinfunction "2_2") (pintype "passive"))
      (node (ref "SW1") (pin "1") (pinfunction "1_1") (pintype "passive"))
      (node (ref "U4") (pin "29") (pinfunction "PC6(~{RESET}/PCINT14)_29") (pintype "bidirectional"))
    )
    (net (code "28") (name "/SCL") (class "Default")
      (node (ref "R1") (pin "1") (pinfunction "1_1") (pintype "passive"))
      (node (ref "R17") (pin "1") (pinfunction "1_1") (pintype "passive"))
      (node (ref "U2") (pin "3") (pinfunction "SCL_3") (pintype "passive"))
      (node (ref "U4") (pin "28") (pinfunction "PC5(ADC5/SCL/PCINT13)_28") (pintype "bidirectional"))
      (node (ref "U7") (pin "7") (pinfunction "SCL_7") (pintype "input"))
    )
    (net (code "29") (name "/SDA") (class "Default")
      (node (ref "R18") (pin "1") (pinfunction "1_1") (pintype "passive"))
      (node (ref "R3") (pin "1") (pinfunction "1_1") (pintype "passive"))
      (node (ref "U2") (pin "4") (pinfunction "SDA_4") (pintype "passive"))
      (node (ref "U4") (pin "27") (pinfunction "PC4(ADC4/SDA/PCINT12)_27") (pintype "bidirectional"))
      (node (ref "U7") (pin "8") (pinfunction "SDA_8") (pintype "bidirectional"))
    )
    (net (code "30") (name "/USB_RX") (class "Default")
      (node (ref "R5") (pin "2") (pinfunction "2_2") (pintype "passive"))
      (node (ref "U1") (pin "25") (pinfunction "RXD_25") (pintype "input"))
      (node (ref "U4") (pin "31") (pinfunction "PD1(TXD/PCINT17)_31") (pintype "bidirectional"))
    )
    (net (code "31") (name "/USB_TX") (class "Default")
      (node (ref "R6") (pin "2") (pinfunction "2_2") (pintype "passive"))
      (node (ref "U1") (pin "26") (pinfunction "TXD_26") (pintype "output"))
      (node (ref "U4") (pin "30") (pinfunction "PD0(RXD/PCINT16)_30") (pintype "bidirectional"))
    )
    (net (code "32") (name "GND") (class "Default")
      (node (ref "C10") (pin "1") (pinfunction "1_1") (pintype "passive"))
      (node (ref "C11") (pin "1") (pinfunction "1_1") (pintype "passive"))
      (node (ref "C12") (pin "1") (pinfunction "C_1") (pintype "passive"))
      (node (ref "C13") (pin "1") (pinfunction "C_1") (pintype "passive"))
      (node (ref "C14") (pin "2") (pinfunction "2_2") (pintype "passive"))
      (node (ref "C15") (pin "2") (pinfunction "2_2") (pintype "passive"))
      (node (ref "C16") (pin "2") (pinfunction "2_2") (pintype "passive"))
      (node (ref "C17") (pin "2") (pinfunction "2_2") (pintype "passive"))
      (node (ref "C18") (pin "2") (pinfunction "2_2") (pintype "passive"))
      (node (ref "C2") (pin "1") (pinfunction "1_1") (pintype "passive"))
      (node (ref "C21") (pin "2") (pinfunction "2_2") (pintype "passive"))
      (node (ref "C22") (pin "2") (pinfunction "2_2") (pintype "passive"))
      (node (ref "C23") (pin "2") (pinfunction "2_2") (pintype "passive"))
      (node (ref "C24") (pin "2") (pinfunction "2_2") (pintype "passive"))
      (node (ref "C25") (pin "2") (pinfunction "2_2") (pintype "passive"))
      (node (ref "C3") (pin "2") (pinfunction "2_2") (pintype "passive"))
      (node (ref "C4") (pin "2") (pinfunction "2_2") (pintype "passive"))
      (node (ref "C5") (pin "1") (pinfunction "1_1") (pintype "passive"))
      (node (ref "C6") (pin "2") (pinfunction "2_2") (pintype "passive"))
      (node (ref "C7") (pin "2") (pinfunction "2_2") (pintype "passive"))
      (node (ref "C8") (pin "2") (pinfunction "2_2") (pintype "passive"))
      (node (ref "C9") (pin "2") (pinfunction "2_2") (pintype "passive"))
      (node (ref "D1") (pin "1") (pinfunction "C_1") (pintype "passive"))
      (node (ref "D10") (pin "1") (pinfunction "C_1") (pintype "passive"))
      (node (ref "D12") (pin "2") (pinfunction "A_2") (pintype "passive"))
      (node (ref "D3") (pin "1") (pinfunction "C_1") (pintype "passive"))
      (node (ref "D4") (pin "2") (pinfunction "A_2") (pintype "passive"))
      (node (ref "D5") (pin "1") (pinfunction "1_1") (pintype "passive"))
      (node (ref "D6") (pin "1") (pinfunction "1_1") (pintype "passive"))
      (node (ref "D7") (pin "1") (pinfunction "1_1") (pintype "passive"))
      (node (ref "D8") (pin "1") (pinfunction "C_1") (pintype "passive"))
      (node (ref "D9") (pin "1") (pinfunction "C_1") (pintype "passive"))
      (node (ref "J1") (pin "5") (pinfunction "GND_5") (pintype "passive"))
      (node (ref "J1") (pin "Shell") (pinfunction "Shield_Shell") (pintype "passive"))
      (node (ref "J2") (pin "1") (pinfunction "1_1") (pintype "passive"))
      (node (ref "Q1") (pin "2") (pinfunction "EMITTER_2") (pintype "passive"))
      (node (ref "R15") (pin "2") (pinfunction "2_2") (pintype "passive"))
      (node (ref "R20") (pin "1") (pinfunction "1_1") (pintype "passive"))
      (node (ref "R21") (pin "1") (pinfunction "1_1") (pintype "passive"))
      (node (ref "S2") (pin "2") (pinfunction "2_2") (pintype "passive"))
      (node (ref "S3") (pin "2") (pinfunction "2_2") (pintype "passive"))
      (node (ref "S4") (pin "2") (pinfunction "2_2") (pintype "passive"))
      (node (ref "S5") (pin "2") (pinfunction "2_2") (pintype "passive"))
      (node (ref "S6") (pin "2") (pinfunction "2_2") (pintype "passive"))
      (node (ref "SW1") (pin "2") (pinfunction "2_2") (pintype "passive"))
      (node (ref "U1") (pin "29") (pinfunction "GND_29") (pintype "power_in"))
      (node (ref "U1") (pin "3") (pinfunction "GND_3") (pintype "power_in"))
      (node (ref "U2") (pin "1") (pinfunction "GND_1") (pintype "passive"))
      (node (ref "U3") (pin "3") (pinfunction "GND_3") (pintype "power_in"))
      (node (ref "U3") (pin "5") (pinfunction "~{ON}/OFF_5") (pintype "input"))
      (node (ref "U3") (pin "6") (pinfunction "TAB_6") (pintype "power_in"))
      (node (ref "U4") (pin "21") (pinfunction "GND_21") (pintype "power_in"))
      (node (ref "U4") (pin "3") (pinfunction "GND_3") (pintype "power_in"))
      (node (ref "U4") (pin "5") (pinfunction "GND_5") (pintype "power_in"))
      (node (ref "U5") (pin "1") (pinfunction "Ground_1") (pintype "power_in"))
      (node (ref "U6") (pin "10") (pinfunction "REF_ADJ_10") (pintype "input"))
      (node (ref "U6") (pin "2") (pinfunction "V-_2") (pintype "power_in"))
      (node (ref "U6") (pin "4") (pinfunction "DIVIDER_LOW_4") (pintype "input"))
      (node (ref "U7") (pin "1") (pinfunction "CTG_1") (pintype "power_in"))
      (node (ref "U7") (pin "4") (pinfunction "GND_4") (pintype "power_in"))
      (node (ref "U7") (pin "6") (pinfunction "QSTRT_6") (pintype "input"))
      (node (ref "U7") (pin "9") (pinfunction "EP_9") (pintype "power_in"))
    )
    (net (code "33") (name "Net-(D1-A)") (class "Default")
      (node (ref "D1") (pin "2") (pinfunction "A_2") (pintype "passive"))
      (node (ref "R2") (pin "2") (pinfunction "2_2") (pintype "passive"))
    )
    (net (code "34") (name "Net-(D2-A)") (class "Default")
      (node (ref "D2") (pin "2") (pinfunction "A_2") (pintype "passive"))
      (node (ref "F1") (pin "2") (pinfunction "2_2") (pintype "passive"))
    )
    (net (code "35") (name "Net-(D3-A)") (class "Default")
      (node (ref "D3") (pin "2") (pinfunction "A_2") (pintype "passive"))
      (node (ref "R4") (pin "2") (pinfunction "2_2") (pintype "passive"))
    )
    (net (code "36") (name "Net-(D4-C)") (class "Default")
      (node (ref "D4") (pin "1") (pinfunction "C_1") (pintype "passive"))
      (node (ref "F1") (pin "1") (pinfunction "1_1") (pintype "passive"))
      (node (ref "S1") (pin "2") (pinfunction "2_2") (pintype "passive"))
    )
    (net (code "37") (name "Net-(D8-A)") (class "Default")
      (node (ref "D8") (pin "2") (pinfunction "A_2") (pintype "passive"))
      (node (ref "R7") (pin "2") (pinfunction "2_2") (pintype "passive"))
    )
    (net (code "38") (name "Net-(D9-A)") (class "Default")
      (node (ref "D9") (pin "2") (pinfunction "A_2") (pintype "passive"))
      (node (ref "R5") (pin "1") (pinfunction "1_1") (pintype "passive"))
    )
    (net (code "39") (name "Net-(D10-A)") (class "Default")
      (node (ref "D10") (pin "2") (pinfunction "A_2") (pintype "passive"))
      (node (ref "R6") (pin "1") (pinfunction "1_1") (pintype "passive"))
    )
    (net (code "40") (name "Net-(D11-A)") (class "Default")
      (node (ref "B1") (pin "2") (pinfunction "2_2") (pintype "passive"))
      (node (ref "D11") (pin "1") (pinfunction "A_1") (pintype "passive"))
      (node (ref "Q1") (pin "3") (pinfunction "COLLECTOR_3") (pintype "passive"))
    )
    (net (code "41") (name "Net-(D12-C)") (class "Default")
      (node (ref "D12") (pin "1") (pinfunction "C_1") (pintype "passive"))
      (node (ref "L1") (pin "1") (pinfunction "1_1") (pintype "passive"))
      (node (ref "U3") (pin "2") (pinfunction "OUT_2") (pintype "power_in"))
    )
    (net (code "42") (name "Net-(J2-Pad2)") (class "Default")
      (node (ref "J2") (pin "2") (pinfunction "2_2") (pintype "passive"))
      (node (ref "S1") (pin "1") (pinfunction "1_1") (pintype "passive"))
    )
    (net (code "43") (name "Net-(Q1-BASE)") (class "Default")
      (node (ref "Q1") (pin "1") (pinfunction "BASE_1") (pintype "passive"))
      (node (ref "R8") (pin "1") (pinfunction "1_1") (pintype "passive"))
    )
    (net (code "44") (name "Net-(U1A-~{DTR})") (class "Default")
      (node (ref "C1") (pin "1") (pinfunction "1_1") (pintype "passive"))
      (node (ref "U1") (pin "28") (pinfunction "~{DTR}_28") (pintype "output"))
    )
    (net (code "45") (name "Net-(U4-AREF)") (class "Default")
      (node (ref "C14") (pin "1") (pinfunction "1_1") (pintype "passive"))
      (node (ref "U4") (pin "20") (pinfunction "AREF_20") (pintype "passive"))
    )
    (net (code "46") (name "Net-(U4-AVCC)") (class "Default")
      (node (ref "C10") (pin "2") (pinfunction "2_2") (pintype "passive"))
      (node (ref "C11") (pin "2") (pinfunction "2_2") (pintype "passive"))
      (node (ref "FB1") (pin "2") (pinfunction "2_2") (pintype "passive"))
      (node (ref "U4") (pin "18") (pinfunction "AVCC_18") (pintype "power_in"))
    )
    (net (code "47") (name "Net-(U6-DIVIDER_HIGH)") (class "Default")
      (node (ref "R15") (pin "1") (pinfunction "1_1") (pintype "passive"))
      (node (ref "U6") (pin "6") (pinfunction "DIVIDER_HIGH_6") (pintype "input"))
      (node (ref "U6") (pin "8") (pinfunction "REF_OUT_8") (pintype "output"))
    )
    (net (code "48") (name "Net-(U6-SIGNAL_IN)") (class "Default")
      (node (ref "R16") (pin "1") (pinfunction "1_1") (pintype "passive"))
      (node (ref "R20") (pin "2") (pinfunction "2_2") (pintype "passive"))
      (node (ref "U6") (pin "5") (pinfunction "SIGNAL_IN_5") (pintype "input"))
    )
    (net (code "49") (name "Net-(U7-CELL)") (class "Default")
      (node (ref "R19") (pin "1") (pinfunction "1_1") (pintype "passive"))
      (node (ref "R21") (pin "2") (pinfunction "2_2") (pintype "passive"))
      (node (ref "U7") (pin "2") (pinfunction "CELL_2") (pintype "passive"))
    )
    (net (code "50") (name "unconnected-(J1-ID-Pad4)") (class "Default")
      (node (ref "J1") (pin "4") (pinfunction "ID_4") (pintype "passive"))
    )
    (net (code "51") (name "unconnected-(S1-Pad3)") (class "Default")
      (node (ref "S1") (pin "3") (pinfunction "3_3") (pintype "passive"))
    )
    (net (code "52") (name "unconnected-(S1-Pad4)") (class "Default")
      (node (ref "S1") (pin "4") (pinfunction "4_4") (pintype "passive"))
    )
    (net (code "53") (name "unconnected-(S1-Pad5)") (class "Default")
      (node (ref "S1") (pin "5") (pinfunction "5_5") (pintype "passive"))
    )
    (net (code "54") (name "unconnected-(S1-Pad6)") (class "Default")
      (node (ref "S1") (pin "6") (pinfunction "6_6") (pintype "passive"))
    )
    (net (code "55") (name "unconnected-(U1A-SUSPEND-Pad12)") (class "Default")
      (node (ref "U1") (pin "12") (pinfunction "SUSPEND_12") (pintype "output"))
    )
    (net (code "56") (name "unconnected-(U1A-~{CTS}-Pad23)") (class "Default")
      (node (ref "U1") (pin "23") (pinfunction "~{CTS}_23") (pintype "input"))
    )
    (net (code "57") (name "unconnected-(U1A-~{DCD}-Pad1)") (class "Default")
      (node (ref "U1") (pin "1") (pinfunction "~{DCD}_1") (pintype "input"))
    )
    (net (code "58") (name "unconnected-(U1A-~{DSR}-Pad27)") (class "Default")
      (node (ref "U1") (pin "27") (pinfunction "~{DSR}_27") (pintype "input"))
    )
    (net (code "59") (name "unconnected-(U1A-~{RI}-Pad2)") (class "Default")
      (node (ref "U1") (pin "2") (pinfunction "~{RI}_2") (pintype "input"))
    )
    (net (code "60") (name "unconnected-(U1A-~{RST}-Pad9)") (class "Default")
      (node (ref "U1") (pin "9") (pinfunction "~{RST}_9") (pintype "bidirectional"))
    )
    (net (code "61") (name "unconnected-(U1A-~{RTS}-Pad24)") (class "Default")
      (node (ref "U1") (pin "24") (pinfunction "~{RTS}_24") (pintype "output"))
    )
    (net (code "62") (name "unconnected-(U1A-~{SUSPEND}-Pad11)") (class "Default")
      (node (ref "U1") (pin "11") (pinfunction "~{SUSPEND}_11") (pintype "output"))
    )
    (net (code "63") (name "unconnected-(U2-DC-Pad6)") (class "Default")
      (node (ref "U2") (pin "6") (pinfunction "DC_6") (pintype "passive"))
    )
    (net (code "64") (name "unconnected-(U2-RES-Pad5)") (class "Default")
      (node (ref "U2") (pin "5") (pinfunction "RES_5") (pintype "passive"))
    )
    (net (code "65") (name "unconnected-(U4-(PCINT20{slash}XCK{slash}T0)PD4-Pad2)") (class "Default")
      (node (ref "U4") (pin "2") (pinfunction "(PCINT20/XCK/T0)PD4_2") (pintype "bidirectional"))
    )
    (net (code "66") (name "unconnected-(U4-(PCINT21{slash}OC0B{slash}T1)PD5-Pad9)") (class "Default")
      (node (ref "U4") (pin "9") (pinfunction "(PCINT21/OC0B/T1)PD5_9") (pintype "bidirectional"))
    )
    (net (code "67") (name "unconnected-(U4-(PCINT23{slash}AIN1)PD7-Pad11)") (class "Default")
      (node (ref "U4") (pin "11") (pinfunction "(PCINT23/AIN1)PD7_11") (pintype "bidirectional"))
    )
    (net (code "68") (name "unconnected-(U4-ADC6-Pad19)") (class "Default")
      (node (ref "U4") (pin "19") (pinfunction "ADC6_19") (pintype "power_in+no_connect"))
    )
    (net (code "69") (name "unconnected-(U4-ADC7-Pad22)") (class "Default")
      (node (ref "U4") (pin "22") (pinfunction "ADC7_22") (pintype "passive+no_connect"))
    )
    (net (code "70") (name "unconnected-(U4-PB5(SCK{slash}PCINT5)-Pad17)") (class "Default")
      (node (ref "U4") (pin "17") (pinfunction "PB5(SCK/PCINT5)_17") (pintype "bidirectional"))
    )
    (net (code "71") (name "unconnected-(U4-PC0(ADC0{slash}PCINT8)-Pad23)") (class "Default")
      (node (ref "U4") (pin "23") (pinfunction "PC0(ADC0/PCINT8)_23") (pintype "bidirectional"))
    )
    (net (code "72") (name "unconnected-(U4-PC1(ADC1{slash}PCINT9)-Pad24)") (class "Default")
      (node (ref "U4") (pin "24") (pinfunction "PC1(ADC1/PCINT9)_24") (pintype "bidirectional"))
    )
    (net (code "73") (name "unconnected-(U4-PC2(ADC2{slash}PCINT10)-Pad25)") (class "Default")
      (node (ref "U4") (pin "25") (pinfunction "PC2(ADC2/PCINT10)_25") (pintype "bidirectional+no_connect"))
    )
    (net (code "74") (name "unconnected-(U4-PC3(ADC3{slash}PCINT11)-Pad26)") (class "Default")
      (node (ref "U4") (pin "26") (pinfunction "PC3(ADC3/PCINT11)_26") (pintype "bidirectional+no_connect"))
    )
    (net (code "75") (name "unconnected-(U4-PD2(INT0{slash}PCINT18)-Pad32)") (class "Default")
      (node (ref "U4") (pin "32") (pinfunction "PD2(INT0/PCINT18)_32") (pintype "bidirectional"))
    )
    (net (code "76") (name "unconnected-(U6-NC-Pad7)") (class "Default")
      (node (ref "U6") (pin "7") (pinfunction "NC_7") (pintype "passive"))
    )
    (net (code "77") (name "unconnected-(U6-NC-Pad9)") (class "Default")
      (node (ref "U6") (pin "9") (pinfunction "NC_9") (pintype "passive"))
    )
  )
)
